# PG03_SHEET1.net
KiCad netlist of a schematic drawn in Altium Designer
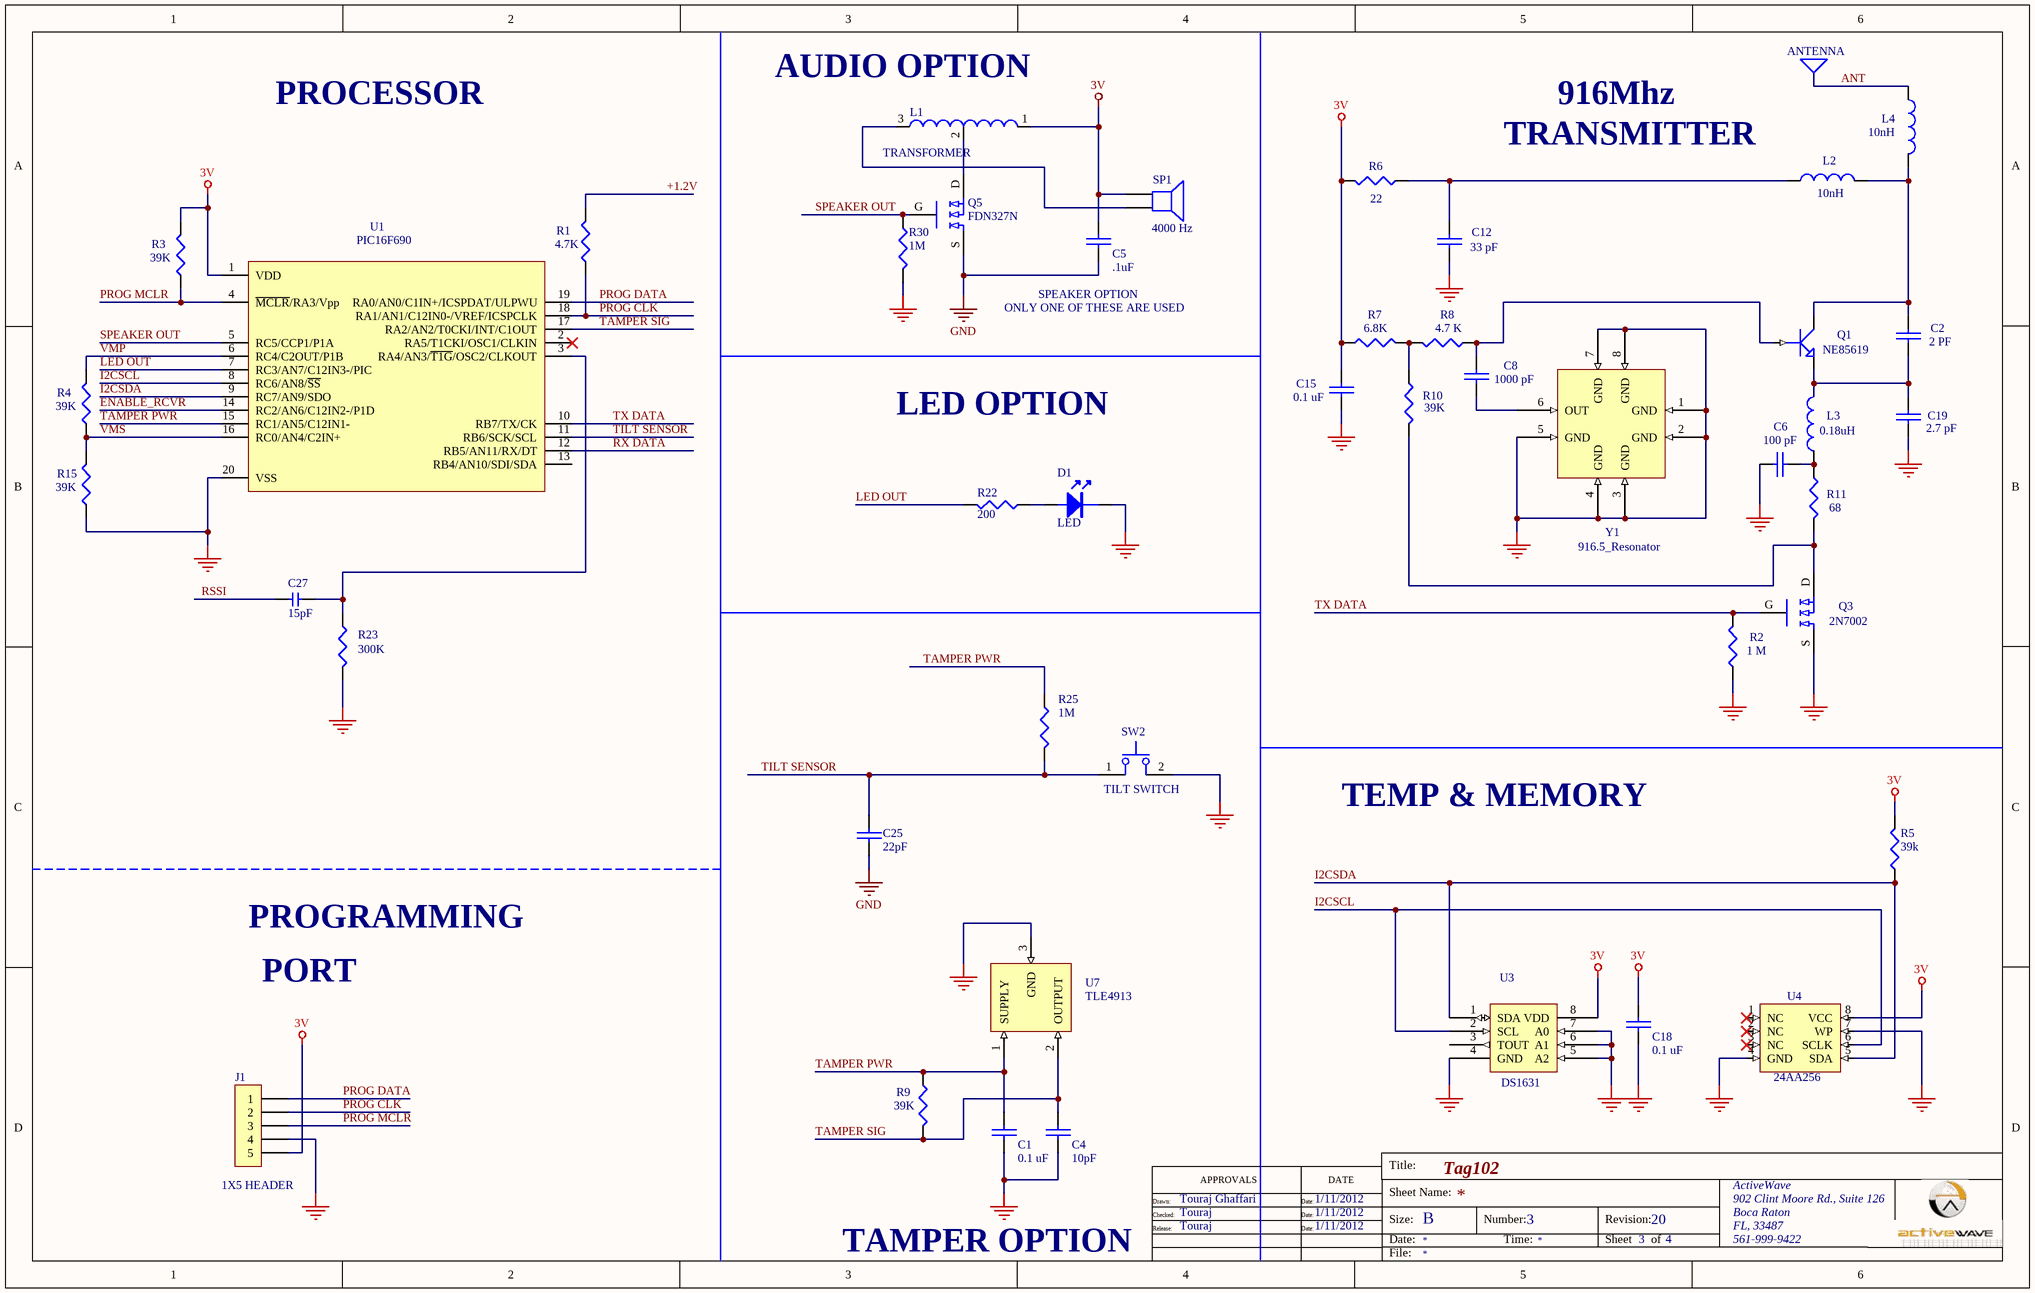
[diagram p0: PG03 SHEET1.schdoc]

(export (version "E")
  (design (tool "Eeschema 10.0.6"))
  (components
    (comp (ref "C1")
      (value "0.1 uF")
      (footprint "0603")
      (description "Capacitor")
      (libsource (lib "*") (part "CAP"))
    )
    (comp (ref "C2")
      (value "2 PF")
      (footprint "0603")
      (description "Capacitor")
      (libsource (lib "*") (part "CAP"))
    )
    (comp (ref "C4")
      (value "10pF")
      (footprint "0603")
      (description "Capacitor")
      (libsource (lib "*") (part "CAP"))
    )
    (comp (ref "C5")
      (value ".1uF")
      (footprint "0603")
      (description "Capacitor")
      (libsource (lib "ActiveWave MasterLib") (part "CAP-0603"))
    )
    (comp (ref "C6")
      (value "100 pF")
      (footprint "0603")
      (description "Capacitor")
      (libsource (lib "*") (part "CAP"))
    )
    (comp (ref "C8")
      (value "1000 pF")
      (footprint "0603")
      (description "Capacitor")
      (libsource (lib "*") (part "CAP"))
    )
    (comp (ref "C12")
      (value "33 pF")
      (footprint "0603")
      (description "Capacitor")
      (libsource (lib "*") (part "CAP"))
    )
    (comp (ref "C15")
      (value "0.1 uF")
      (footprint "0603")
      (description "Capacitor")
      (libsource (lib "*") (part "CAP"))
    )
    (comp (ref "C18")
      (value "0.1 uF")
      (footprint "0603")
      (description "Capacitor")
      (libsource (lib "*") (part "CAP"))
    )
    (comp (ref "C19")
      (value "2.7 pF")
      (footprint "0603")
      (description "Capacitor")
      (libsource (lib "*") (part "CAP"))
    )
    (comp (ref "C25")
      (value "22pF")
      (footprint "0603")
      (description "Capacitor")
      (libsource (lib "*") (part "CAP"))
    )
    (comp (ref "C27") (value "15pF") (footprint "0603") (libsource (lib "*") (part "C")))
    (comp (ref "D1") (value "LED") (footprint "LED STANLEY H_1105W") (libsource (lib "*") (part "LED")))
    (comp (ref "J1")
      (value "1X5 HEADER")
      (footprint "1X5 HEADER")
      (description "Connector")
      (libsource (lib "*") (part "CON5"))
    )
    (comp (ref "L1")
      (value "TRANSFORMER")
      (footprint "COIL_6mmx6mm_011012")
      (libsource (lib "ActiveWave MasterLib") (part "INDUCTOR_V2"))
    )
    (comp (ref "L2") (value "10nH") (footprint "0603") (libsource (lib "*") (part "INDUCTOR")))
    (comp (ref "L3") (value "0.18uH") (footprint "0603") (libsource (lib "*") (part "INDUCTOR")))
    (comp (ref "L4") (value "10nH") (footprint "0603") (libsource (lib "*") (part "INDUCTOR")))
    (comp (ref "Q1")
      (value "NE85619")
      (footprint "3 PIN ULTRA SUPER MINI MOLD")
      (description "NPN Transistor")
      (libsource (lib "*") (part "NPN1"))
    )
    (comp (ref "Q3") (value "2N7002") (libsource (lib "*") (part "FET 2")))
    (comp (ref "Q5")
      (value "FDN327N")
      (footprint "SOT23 FET")
      (description "20V N-Channel MOSFET")
      (fields (field (name "MANUFACTURER") "FAIRCHILD"))
      (libsource (lib "ActiveWave MasterLib") (part "FDN327N"))
    )
    (comp (ref "R1") (value "4.7K") (footprint "0603") (libsource (lib "*") (part "RESISTOR")))
    (comp (ref "R2") (value "1 M") (footprint "0603") (libsource (lib "*") (part "RESISTOR")))
    (comp (ref "R3") (value "39K") (footprint "0603") (libsource (lib "*") (part "RESISTOR")))
    (comp (ref "R4") (value "39K") (footprint "0603") (libsource (lib "*") (part "RESISTOR")))
    (comp (ref "R5") (value "39k") (footprint "0603") (libsource (lib "*") (part "RESISTOR")))
    (comp (ref "R6") (value "22") (footprint "0603") (libsource (lib "*") (part "RESISTOR")))
    (comp (ref "R7") (value "6.8K") (footprint "0603") (libsource (lib "*") (part "RESISTOR")))
    (comp (ref "R8") (value "4.7 K") (footprint "0603") (libsource (lib "*") (part "RESISTOR")))
    (comp (ref "R9") (value "39K") (footprint "0603") (libsource (lib "*") (part "RESISTOR")))
    (comp (ref "R10") (value "39K") (footprint "0603") (libsource (lib "*") (part "RESISTOR")))
    (comp (ref "R11") (value "68") (footprint "0603") (libsource (lib "*") (part "RES1")))
    (comp (ref "R15") (value "39K") (footprint "0603") (libsource (lib "*") (part "RESISTOR")))
    (comp (ref "R22") (value "200") (footprint "0603") (libsource (lib "*") (part "RES1")))
    (comp (ref "R23") (value "300K") (footprint "0603") (libsource (lib "*") (part "RESISTOR")))
    (comp (ref "R25") (value "1M") (footprint "0603") (libsource (lib "*") (part "RESISTOR")))
    (comp (ref "R30")
      (value "1M")
      (footprint "0603")
      (libsource (lib "ActiveWave MasterLib") (part "RES-0402"))
    )
    (comp (ref "SP1")
      (value "4000 Hz")
      (footprint "SPEAKER 12mmx12mm_011012")
      (description "Surface Mount Transducer")
      (fields (field (name "MANUFACTURER") "PUI Audio"))
      (libsource (lib "ActiveWave MasterLib") (part "SMT-1028-S-R"))
    )
    (comp (ref "SW2")
      (value "TILT SWITCH")
      (footprint "SQ-SEN-DUAL1")
      (libsource (lib "Common") (part "SWITCH PB"))
    )
    (comp (ref "U1") (value "PIC16F690") (libsource (lib "*") (part "PIC16F690")))
    (comp (ref "U3") (value "DS1631") (footprint "SO8 SMALL") (libsource (lib "*") (part "DS1631")))
    (comp (ref "U4") (value "24AA256") (footprint "SO8") (libsource (lib "*") (part "24AA256")))
    (comp (ref "U7") (value "TLE4913") (footprint "SOT23W") (libsource (lib "*") (part "HALL EFFECT SWITCH")))
    (comp (ref "Y1")
      (value "916.5_Resonator")
      (footprint "RESONATOR")
      (libsource (lib "*") (part "RESONATOR"))
    )
  )
  (nets
    (net (code "1") (name "/+1.2V") (class "Default")
      (node (ref "R1") (pin "2") (pinfunction "2_2") (pintype "passive"))
    )
    (net (code "2") (name "/ANT") (class "Default")
      (node (ref "L4") (pin "1") (pinfunction "1_1") (pintype "passive"))
    )
    (net (code "3") (name "/ENABLE_RCVR") (class "Default")
      (node (ref "U1") (pin "14") (pinfunction "RC2/AN6/C12IN2-/P1D_14") (pintype "passive"))
    )
    (net (code "4") (name "/I2CSCL") (class "Default")
      (node (ref "U1") (pin "8") (pinfunction "RC6/AN8/~{SS}_8") (pintype "passive"))
      (node (ref "U3") (pin "2") (pinfunction "SCL_2") (pintype "input"))
      (node (ref "U4") (pin "6") (pinfunction "SCLK_6") (pintype "input"))
    )
    (net (code "5") (name "/I2CSDA") (class "Default")
      (node (ref "R5") (pin "1") (pinfunction "1_1") (pintype "passive"))
      (node (ref "U1") (pin "9") (pinfunction "RC7/AN9/SDO_9") (pintype "passive"))
      (node (ref "U3") (pin "1") (pinfunction "SDA_1") (pintype "bidirectional"))
      (node (ref "U4") (pin "5") (pinfunction "SDA_5") (pintype "input"))
    )
    (net (code "6") (name "/LED OUT") (class "Default")
      (node (ref "R22") (pin "2") (pinfunction "2_2") (pintype "passive"))
      (node (ref "U1") (pin "7") (pinfunction "RC3/AN7/C12IN3-/PIC_7") (pintype "passive"))
    )
    (net (code "7") (name "/PROG CLK") (class "Default")
      (node (ref "J1") (pin "2") (pinfunction "2_2") (pintype "passive"))
      (node (ref "R1") (pin "1") (pinfunction "1_1") (pintype "passive"))
      (node (ref "U1") (pin "18") (pinfunction "RA1/AN1/C12IN0-/VREF/ICSPCLK_18") (pintype "passive"))
    )
    (net (code "8") (name "/PROG DATA") (class "Default")
      (node (ref "J1") (pin "1") (pinfunction "1_1") (pintype "passive"))
      (node (ref "U1") (pin "19") (pinfunction "RA0/AN0/C1IN+/ICSPDAT/ULPWU_19") (pintype "passive"))
    )
    (net (code "9") (name "/PROG MCLR") (class "Default")
      (node (ref "J1") (pin "3") (pinfunction "3_3") (pintype "passive"))
      (node (ref "R3") (pin "1") (pinfunction "1_1") (pintype "passive"))
      (node (ref "U1") (pin "4") (pinfunction "~{MCLR}/RA3/Vpp_4") (pintype "passive"))
    )
    (net (code "10") (name "/RSSI") (class "Default")
      (node (ref "C27") (pin "2") (pinfunction "2_2") (pintype "passive"))
    )
    (net (code "11") (name "/RX DATA") (class "Default")
      (node (ref "U1") (pin "12") (pinfunction "RB5/AN11/RX/DT_12") (pintype "passive"))
    )
    (net (code "12") (name "/SPEAKER OUT") (class "Default")
      (node (ref "Q5") (pin "G") (pinfunction "G_G") (pintype "passive"))
      (node (ref "R30") (pin "1") (pinfunction "1_1") (pintype "passive"))
      (node (ref "U1") (pin "5") (pinfunction "RC5/CCP1/P1A_5") (pintype "passive"))
    )
    (net (code "13") (name "/TAMPER PWR") (class "Default")
      (node (ref "C1") (pin "1") (pinfunction "1_1") (pintype "passive"))
      (node (ref "R25") (pin "1") (pinfunction "1_1") (pintype "passive"))
      (node (ref "R9") (pin "1") (pinfunction "1_1") (pintype "passive"))
      (node (ref "U1") (pin "15") (pinfunction "RC1/AN5/C12IN1-_15") (pintype "passive"))
      (node (ref "U7") (pin "1") (pinfunction "SUPPLY_1") (pintype "input"))
    )
    (net (code "14") (name "/TAMPER SIG") (class "Default")
      (node (ref "C4") (pin "1") (pinfunction "1_1") (pintype "passive"))
      (node (ref "R9") (pin "2") (pinfunction "2_2") (pintype "passive"))
      (node (ref "U1") (pin "17") (pinfunction "RA2/AN2/T0CKI/INT/C1OUT_17") (pintype "passive"))
      (node (ref "U7") (pin "2") (pinfunction "OUTPUT_2") (pintype "input"))
    )
    (net (code "15") (name "/TILT SENSOR") (class "Default")
      (node (ref "C25") (pin "1") (pinfunction "1_1") (pintype "passive"))
      (node (ref "R25") (pin "2") (pinfunction "2_2") (pintype "passive"))
      (node (ref "SW2") (pin "1") (pinfunction "1_1") (pintype "passive"))
      (node (ref "U1") (pin "11") (pinfunction "RB6/SCK/SCL_11") (pintype "passive"))
    )
    (net (code "16") (name "/TX DATA") (class "Default")
      (node (ref "Q3") (pin "G") (pinfunction "G_G") (pintype "passive"))
      (node (ref "R2") (pin "2") (pinfunction "2_2") (pintype "passive"))
      (node (ref "U1") (pin "10") (pinfunction "RB7/TX/CK_10") (pintype "passive"))
    )
    (net (code "17") (name "/VMP") (class "Default")
      (node (ref "R4") (pin "2") (pinfunction "2_2") (pintype "passive"))
      (node (ref "U1") (pin "6") (pinfunction "RC4/C2OUT/P1B_6") (pintype "passive"))
    )
    (net (code "18") (name "/VMS") (class "Default")
      (node (ref "R15") (pin "2") (pinfunction "2_2") (pintype "passive"))
      (node (ref "R4") (pin "1") (pinfunction "1_1") (pintype "passive"))
      (node (ref "U1") (pin "16") (pinfunction "RC0/AN4/C2IN+_16") (pintype "passive"))
    )
    (net (code "19") (name "3V") (class "Default")
      (node (ref "C15") (pin "1") (pinfunction "1_1") (pintype "passive"))
      (node (ref "C18") (pin "1") (pinfunction "1_1") (pintype "passive"))
      (node (ref "C5") (pin "1") (pinfunction "1_1") (pintype "passive"))
      (node (ref "J1") (pin "5") (pinfunction "5_5") (pintype "passive"))
      (node (ref "L1") (pin "1") (pinfunction "1_1") (pintype "passive"))
      (node (ref "R3") (pin "2") (pinfunction "2_2") (pintype "passive"))
      (node (ref "R5") (pin "2") (pinfunction "2_2") (pintype "passive"))
      (node (ref "R6") (pin "2") (pinfunction "2_2") (pintype "passive"))
      (node (ref "R7") (pin "1") (pinfunction "1_1") (pintype "passive"))
      (node (ref "SP1") (pin "1") (pinfunction "1_1") (pintype "passive"))
      (node (ref "U1") (pin "1") (pinfunction "VDD_1") (pintype "passive"))
      (node (ref "U3") (pin "8") (pinfunction "VDD_8") (pintype "power_in"))
      (node (ref "U4") (pin "8") (pinfunction "VCC_8") (pintype "input"))
    )
    (net (code "20") (name "GND") (class "Default")
      (node (ref "C1") (pin "2") (pinfunction "2_2") (pintype "passive"))
      (node (ref "C12") (pin "2") (pinfunction "2_2") (pintype "passive"))
      (node (ref "C15") (pin "2") (pinfunction "2_2") (pintype "passive"))
      (node (ref "C18") (pin "2") (pinfunction "2_2") (pintype "passive"))
      (node (ref "C19") (pin "2") (pinfunction "2_2") (pintype "passive"))
      (node (ref "C25") (pin "2") (pinfunction "2_2") (pintype "passive"))
      (node (ref "C4") (pin "2") (pinfunction "2_2") (pintype "passive"))
      (node (ref "C5") (pin "2") (pinfunction "2_2") (pintype "passive"))
      (node (ref "C6") (pin "1") (pinfunction "1_1") (pintype "passive"))
      (node (ref "D1") (pin "K") (pinfunction "K_K") (pintype "passive"))
      (node (ref "J1") (pin "4") (pinfunction "4_4") (pintype "passive"))
      (node (ref "Q3") (pin "S") (pinfunction "S_S") (pintype "passive"))
      (node (ref "Q5") (pin "S") (pinfunction "S_S") (pintype "passive"))
      (node (ref "R15") (pin "1") (pinfunction "1_1") (pintype "passive"))
      (node (ref "R2") (pin "1") (pinfunction "1_1") (pintype "passive"))
      (node (ref "R23") (pin "2") (pinfunction "2_2") (pintype "passive"))
      (node (ref "R30") (pin "2") (pinfunction "2_2") (pintype "passive"))
      (node (ref "SW2") (pin "2") (pinfunction "2_2") (pintype "passive"))
      (node (ref "U1") (pin "20") (pinfunction "VSS_20") (pintype "passive"))
      (node (ref "U3") (pin "4") (pinfunction "GND_4") (pintype "power_in"))
      (node (ref "U3") (pin "5") (pinfunction "A2_5") (pintype "input"))
      (node (ref "U3") (pin "6") (pinfunction "A1_6") (pintype "input"))
      (node (ref "U3") (pin "7") (pinfunction "A0_7") (pintype "input"))
      (node (ref "U4") (pin "4") (pinfunction "GND_4") (pintype "input"))
      (node (ref "U4") (pin "7") (pinfunction "WP_7") (pintype "input"))
      (node (ref "U7") (pin "3") (pinfunction "GND_3") (pintype "input"))
      (node (ref "Y1") (pin "1") (pinfunction "GND_1") (pintype "input"))
      (node (ref "Y1") (pin "2") (pinfunction "GND_2") (pintype "input"))
      (node (ref "Y1") (pin "3") (pinfunction "GND_3") (pintype "input"))
      (node (ref "Y1") (pin "4") (pinfunction "GND_4") (pintype "input"))
      (node (ref "Y1") (pin "5") (pinfunction "GND_5") (pintype "input"))
      (node (ref "Y1") (pin "7") (pinfunction "GND_7") (pintype "input"))
      (node (ref "Y1") (pin "8") (pinfunction "GND_8") (pintype "input"))
    )
    (net (code "21") (name "Net-(C2-Pad1)") (class "Default")
      (node (ref "C2") (pin "1") (pinfunction "1_1") (pintype "passive"))
      (node (ref "L2") (pin "2") (pinfunction "2_2") (pintype "passive"))
      (node (ref "L4") (pin "2") (pinfunction "2_2") (pintype "passive"))
      (node (ref "Q1") (pin "C") (pinfunction "C_C") (pintype "passive"))
    )
    (net (code "22") (name "Net-(C6-Pad2)") (class "Default")
      (node (ref "C6") (pin "2") (pinfunction "2_2") (pintype "passive"))
      (node (ref "L3") (pin "1") (pinfunction "1_1") (pintype "passive"))
      (node (ref "R11") (pin "1") (pinfunction "1_1") (pintype "passive"))
    )
    (net (code "23") (name "Net-(C8-Pad1)") (class "Default")
      (node (ref "C8") (pin "1") (pinfunction "1_1") (pintype "passive"))
      (node (ref "Q1") (pin "B") (pinfunction "B_B") (pintype "input"))
      (node (ref "R8") (pin "1") (pinfunction "1_1") (pintype "passive"))
    )
    (net (code "24") (name "Net-(C12-Pad1)") (class "Default")
      (node (ref "C12") (pin "1") (pinfunction "1_1") (pintype "passive"))
      (node (ref "L2") (pin "1") (pinfunction "1_1") (pintype "passive"))
      (node (ref "R6") (pin "1") (pinfunction "1_1") (pintype "passive"))
    )
    (net (code "25") (name "Net-(C19-Pad1)") (class "Default")
      (node (ref "C19") (pin "1") (pinfunction "1_1") (pintype "passive"))
      (node (ref "C2") (pin "2") (pinfunction "2_2") (pintype "passive"))
      (node (ref "L3") (pin "2") (pinfunction "2_2") (pintype "passive"))
      (node (ref "Q1") (pin "E") (pinfunction "E_E") (pintype "passive"))
    )
    (net (code "26") (name "Net-(D1-PadA)") (class "Default")
      (node (ref "D1") (pin "A") (pinfunction "A_A") (pintype "passive"))
      (node (ref "R22") (pin "1") (pinfunction "1_1") (pintype "passive"))
    )
    (net (code "27") (name "Net-(L1-Pad2)") (class "Default")
      (node (ref "L1") (pin "2") (pinfunction "2_2") (pintype "passive"))
      (node (ref "Q5") (pin "D") (pinfunction "D_D") (pintype "passive"))
    )
    (net (code "28") (name "Net-(L1-Pad3)") (class "Default")
      (node (ref "L1") (pin "3") (pinfunction "3_3") (pintype "passive"))
      (node (ref "SP1") (pin "2") (pinfunction "2_2") (pintype "passive"))
    )
    (net (code "29") (name "Net-(Q3-PadD)") (class "Default")
      (node (ref "Q3") (pin "D") (pinfunction "D_D") (pintype "passive"))
      (node (ref "R10") (pin "2") (pinfunction "2_2") (pintype "passive"))
      (node (ref "R11") (pin "2") (pinfunction "2_2") (pintype "passive"))
    )
    (net (code "30") (name "Net-(R10-Pad1)") (class "Default")
      (node (ref "R10") (pin "1") (pinfunction "1_1") (pintype "passive"))
      (node (ref "R7") (pin "2") (pinfunction "2_2") (pintype "passive"))
      (node (ref "R8") (pin "2") (pinfunction "2_2") (pintype "passive"))
    )
    (net (code "31") (name "Net-(U1-RA4{slash}AN3{slash}~{T1G}{slash}OSC2{slash}CLKOUT)") (class "Default")
      (node (ref "C27") (pin "1") (pinfunction "1_1") (pintype "passive"))
      (node (ref "R23") (pin "1") (pinfunction "1_1") (pintype "passive"))
      (node (ref "U1") (pin "3") (pinfunction "RA4/AN3/~{T1G}/OSC2/CLKOUT_3") (pintype "passive"))
    )
    (net (code "32") (name "Net-(Y1-OUT)") (class "Default")
      (node (ref "C8") (pin "2") (pinfunction "2_2") (pintype "passive"))
      (node (ref "Y1") (pin "6") (pinfunction "OUT_6") (pintype "input"))
    )
    (net (code "33") (name "unconnected-(U1-RA5{slash}T1CKI{slash}OSC1{slash}CLKIN-Pad2)") (class "Default")
      (node (ref "U1") (pin "2") (pinfunction "RA5/T1CKI/OSC1/CLKIN_2") (pintype "passive+no_connect"))
    )
    (net (code "34") (name "unconnected-(U1-RB4{slash}AN10{slash}SDI{slash}SDA-Pad13)") (class "Default")
      (node (ref "U1") (pin "13") (pinfunction "RB4/AN10/SDI/SDA_13") (pintype "passive"))
    )
    (net (code "35") (name "unconnected-(U3-TOUT-Pad3)") (class "Default")
      (node (ref "U3") (pin "3") (pinfunction "TOUT_3") (pintype "output"))
    )
    (net (code "36") (name "unconnected-(U4-NC-Pad1)") (class "Default")
      (node (ref "U4") (pin "1") (pinfunction "NC_1") (pintype "input+no_connect"))
    )
    (net (code "37") (name "unconnected-(U4-NC-Pad2)") (class "Default")
      (node (ref "U4") (pin "2") (pinfunction "NC_2") (pintype "input+no_connect"))
    )
    (net (code "38") (name "unconnected-(U4-NC-Pad3)") (class "Default")
      (node (ref "U4") (pin "3") (pinfunction "NC_3") (pintype "input+no_connect"))
    )
  )
)
